# Sheet1.net
KiCad netlist of a schematic drawn in Altium Designer
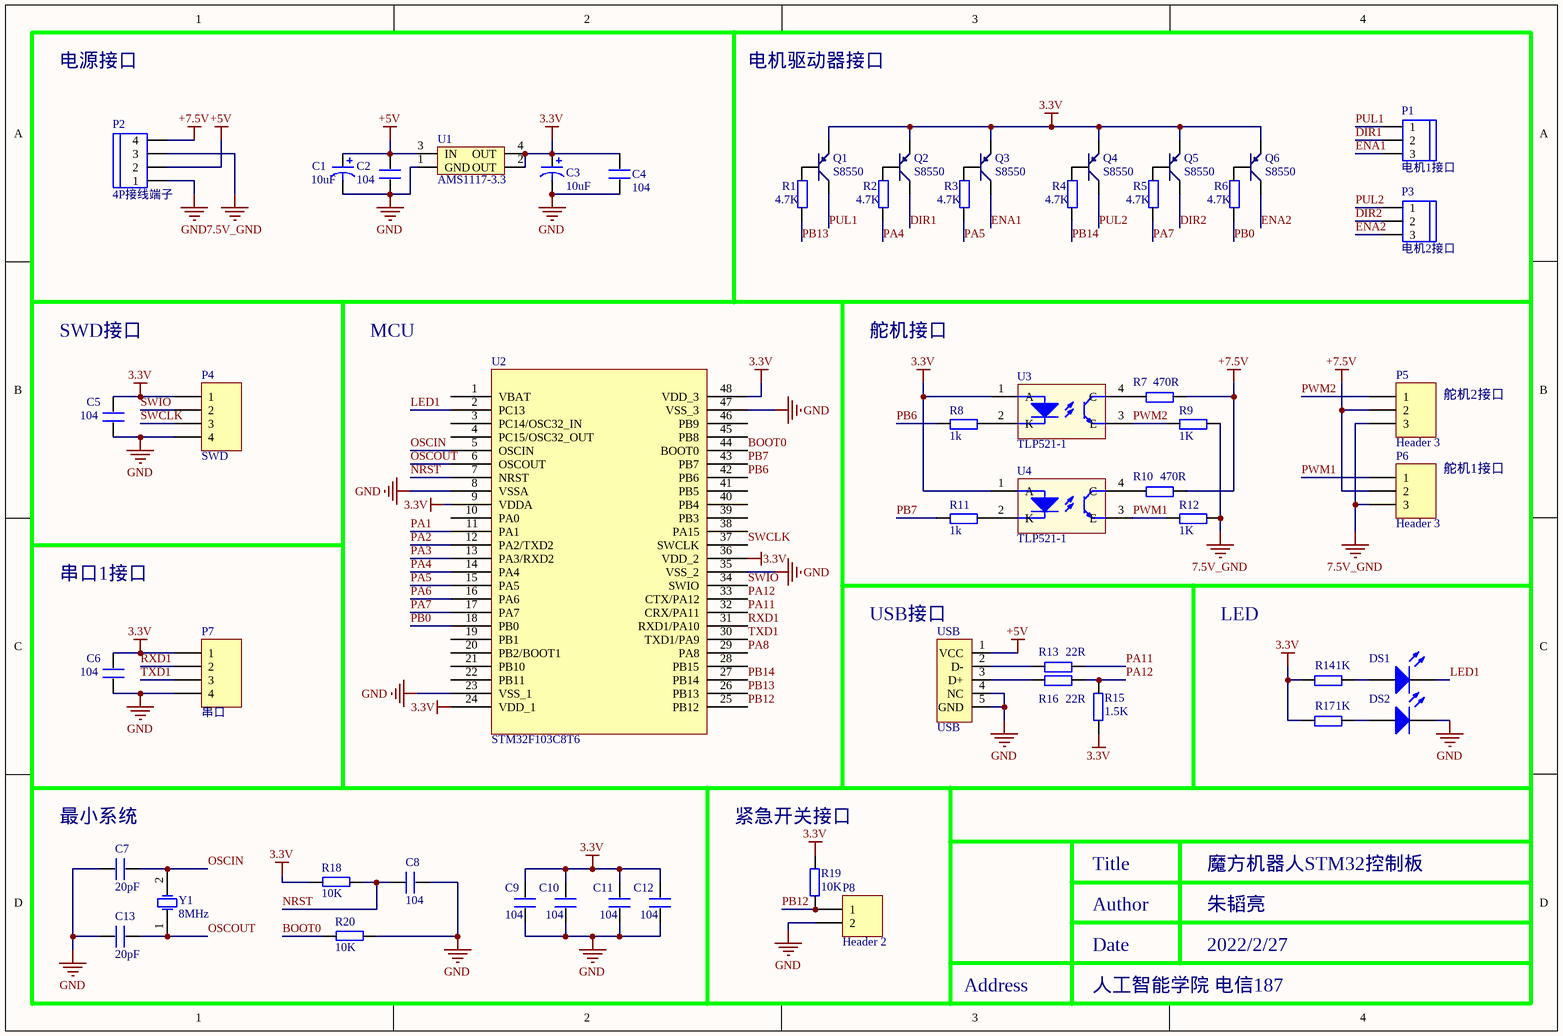
[diagram p0: Sheet1.SchDoc]

(export (version "E")
  (design (tool "Eeschema 10.0.6"))
  (components
    (comp (ref "C1")
      (value "10uF")
      (footprint "钽电容")
      (fields (field (name "Comment") "Cap Pol"))
      (libsource (lib "mylib") (part "Cap Pol"))
    )
    (comp (ref "C2") (value "104") (footprint "0805C") (libsource (lib "Explorer STM32F407封装库") (part "C")))
    (comp (ref "C3")
      (value "10uF")
      (footprint "钽电容")
      (fields (field (name "Comment") "Cap Pol"))
      (libsource (lib "mylib") (part "Cap Pol"))
    )
    (comp (ref "C4") (value "104") (footprint "0805C") (libsource (lib "Explorer STM32F407封装库") (part "C")))
    (comp (ref "C5") (value "104") (footprint "0805C") (libsource (lib "Explorer STM32F407封装库") (part "C")))
    (comp (ref "C6") (value "104") (footprint "0805C") (libsource (lib "Explorer STM32F407封装库") (part "C")))
    (comp (ref "C7") (value "20pF") (footprint "0805C") (libsource (lib "Explorer STM32F407封装库") (part "C")))
    (comp (ref "C8") (value "104") (footprint "0805C") (libsource (lib "Explorer STM32F407封装库") (part "C")))
    (comp (ref "C9") (value "104") (footprint "0805C") (libsource (lib "Explorer STM32F407封装库") (part "C")))
    (comp (ref "C10") (value "104") (footprint "0805C") (libsource (lib "Explorer STM32F407封装库") (part "C")))
    (comp (ref "C11") (value "104") (footprint "0805C") (libsource (lib "Explorer STM32F407封装库") (part "C")))
    (comp (ref "C12") (value "104") (footprint "0805C") (libsource (lib "Explorer STM32F407封装库") (part "C")))
    (comp (ref "C13") (value "20pF") (footprint "0805C") (libsource (lib "Explorer STM32F407封装库") (part "C")))
    (comp (ref "DS1")
      (value "LED1")
      (footprint "SMDLED")
      (description "Typical RED, GREEN, YELLOW, AMBER GaAs LED")
      (fields (field (name "PUBLISHER") "Altium Limited"))
      (libsource (lib "EliteSTM32封装库") (part "LED2"))
    )
    (comp (ref "DS2")
      (value "LED1")
      (footprint "SMDLED")
      (description "Typical RED, GREEN, YELLOW, AMBER GaAs LED")
      (fields (field (name "PUBLISHER") "Altium Limited"))
      (libsource (lib "EliteSTM32封装库") (part "LED2"))
    )
    (comp (ref "P1") (value "电机1接口") (footprint "KF301-3P") (libsource (lib "mylib") (part "3P接线端子")))
    (comp (ref "P2") (value "4P接线端子") (footprint "KF301-4P") (libsource (lib "mylib") (part "4P接线端子")))
    (comp (ref "P3") (value "电机2接口") (footprint "KF301-3P") (libsource (lib "mylib") (part "3P接线端子")))
    (comp (ref "P4")
      (value "SWD")
      (footprint "HDR1X4")
      (description "Header, 4-Pin")
      (fields (field (name "PUBLISHER") "Altium Limited"))
      (libsource (lib "Miscellaneous Connectors") (part "Header 4"))
    )
    (comp (ref "P5")
      (value "Header 3")
      (footprint "HDR1X3")
      (description "Header, 3-Pin")
      (fields (field (name "PUBLISHER") "Altium Limited"))
      (libsource (lib "Miscellaneous Connectors") (part "Header 3"))
    )
    (comp (ref "P6")
      (value "Header 3")
      (footprint "HDR1X3")
      (description "Header, 3-Pin")
      (fields (field (name "PUBLISHER") "Altium Limited"))
      (libsource (lib "Miscellaneous Connectors") (part "Header 3"))
    )
    (comp (ref "P7")
      (value "串口")
      (footprint "HDR1X4")
      (description "Header, 4-Pin")
      (fields (field (name "PUBLISHER") "Altium Limited"))
      (libsource (lib "Miscellaneous Connectors") (part "Header 4"))
    )
    (comp (ref "P8")
      (value "Header 2")
      (footprint "HDR1X2")
      (description "Header, 2-Pin")
      (fields (field (name "PUBLISHER") "Altium Limited"))
      (libsource (lib "Miscellaneous Connectors") (part "Header 2"))
    )
    (comp (ref "Q1")
      (value "S8550")
      (footprint "SOT-23R")
      (description "8550/BCW68")
      (libsource (lib "EliteSTM32封装库") (part "PNP"))
    )
    (comp (ref "Q2")
      (value "S8550")
      (footprint "SOT-23R")
      (description "8550/BCW68")
      (libsource (lib "EliteSTM32封装库") (part "PNP"))
    )
    (comp (ref "Q3")
      (value "S8550")
      (footprint "SOT-23R")
      (description "8550/BCW68")
      (libsource (lib "EliteSTM32封装库") (part "PNP"))
    )
    (comp (ref "Q4")
      (value "S8550")
      (footprint "SOT-23R")
      (description "8550/BCW68")
      (libsource (lib "EliteSTM32封装库") (part "PNP"))
    )
    (comp (ref "Q5")
      (value "S8550")
      (footprint "SOT-23R")
      (description "8550/BCW68")
      (libsource (lib "EliteSTM32封装库") (part "PNP"))
    )
    (comp (ref "Q6")
      (value "S8550")
      (footprint "SOT-23R")
      (description "8550/BCW68")
      (libsource (lib "EliteSTM32封装库") (part "PNP"))
    )
    (comp (ref "R1") (value "4.7K") (footprint "0805") (libsource (lib "EliteSTM32封装库") (part "R_1")))
    (comp (ref "R2") (value "4.7K") (footprint "0805") (libsource (lib "EliteSTM32封装库") (part "R_1")))
    (comp (ref "R3") (value "4.7K") (footprint "0805") (libsource (lib "EliteSTM32封装库") (part "R_1")))
    (comp (ref "R4") (value "4.7K") (footprint "0805") (libsource (lib "EliteSTM32封装库") (part "R_1")))
    (comp (ref "R5") (value "4.7K") (footprint "0805") (libsource (lib "EliteSTM32封装库") (part "R_1")))
    (comp (ref "R6") (value "4.7K") (footprint "0805") (libsource (lib "EliteSTM32封装库") (part "R_1")))
    (comp (ref "R7") (value "470R") (footprint "0805") (libsource (lib "EliteSTM32封装库") (part "R_1")))
    (comp (ref "R8") (value "1k") (footprint "0805") (libsource (lib "EliteSTM32封装库") (part "R_1")))
    (comp (ref "R9") (value "1K") (footprint "0805") (libsource (lib "EliteSTM32封装库") (part "R_1")))
    (comp (ref "R10") (value "470R") (footprint "0805") (libsource (lib "EliteSTM32封装库") (part "R_1")))
    (comp (ref "R11") (value "1k") (footprint "0805") (libsource (lib "EliteSTM32封装库") (part "R_1")))
    (comp (ref "R12") (value "1K") (footprint "0805") (libsource (lib "EliteSTM32封装库") (part "R_1")))
    (comp (ref "R13") (value "22R") (footprint "0805") (libsource (lib "EliteSTM32封装库") (part "R_1")))
    (comp (ref "R14") (value "1K") (footprint "0805") (libsource (lib "EliteSTM32封装库") (part "R_1")))
    (comp (ref "R15") (value "1.5K") (footprint "0805") (libsource (lib "EliteSTM32封装库") (part "R_1")))
    (comp (ref "R16") (value "22R") (footprint "0805") (libsource (lib "EliteSTM32封装库") (part "R_1")))
    (comp (ref "R17") (value "1K") (footprint "0805") (libsource (lib "EliteSTM32封装库") (part "R_1")))
    (comp (ref "R18") (value "10K") (footprint "0805") (libsource (lib "EliteSTM32封装库") (part "R_1")))
    (comp (ref "R19") (value "10K") (footprint "0805") (libsource (lib "EliteSTM32封装库") (part "R_1")))
    (comp (ref "R20") (value "10K") (footprint "0805") (libsource (lib "EliteSTM32封装库") (part "R_1")))
    (comp (ref "U1")
      (value "AMS1117-3.3")
      (footprint "AMS1117")
      (libsource (lib "EliteSTM32封装库") (part "AMS1117"))
    )
    (comp (ref "U2")
      (value "STM32F103C8T6")
      (footprint "LQF48")
      (libsource (lib "mylib") (part "STM32F103C8T6"))
    )
    (comp (ref "U3")
      (value "TLP521-1")
      (footprint "SOP-4_(TLP521)")
      (libsource (lib "mylib") (part "TLP521-1"))
    )
    (comp (ref "U4")
      (value "TLP521-1")
      (footprint "SOP-4_(TLP521)")
      (libsource (lib "mylib") (part "TLP521-1"))
    )
    (comp (ref "USB")
      (value "USB")
      (footprint "USB/SM0.8-6H5")
      (libsource (lib "EliteSTM32封装库") (part "USB5"))
    )
    (comp (ref "Y1") (value "8MHz") (footprint "SMD-5032") (libsource (lib "EliteSTM32封装库") (part "XTAL")))
  )
  (nets
    (net (code "1") (name "+5V") (class "Default")
      (node (ref "C1") (pin "1") (pinfunction "1_1") (pintype "passive"))
      (node (ref "C2") (pin "2") (pintype "passive"))
      (node (ref "P2") (pin "2") (pinfunction "2_2") (pintype "passive"))
      (node (ref "U1") (pin "3") (pinfunction "IN_3") (pintype "passive"))
      (node (ref "USB") (pin "1") (pinfunction "VCC_1") (pintype "passive"))
    )
    (net (code "2") (name "+7.5V") (class "Default")
      (node (ref "P2") (pin "4") (pinfunction "4_4") (pintype "passive"))
      (node (ref "P5") (pin "2") (pinfunction "2_2") (pintype "passive"))
      (node (ref "P6") (pin "2") (pinfunction "2_2") (pintype "passive"))
      (node (ref "R10") (pin "2") (pintype "passive"))
      (node (ref "R7") (pin "2") (pintype "passive"))
    )
    (net (code "3") (name "/BOOT0") (class "Default")
      (node (ref "R20") (pin "2") (pintype "passive"))
      (node (ref "U2") (pin "44") (pinfunction "BOOT0_44") (pintype "passive"))
    )
    (net (code "4") (name "/DIR1") (class "Default")
      (node (ref "P1") (pin "2") (pinfunction "2_2") (pintype "passive"))
      (node (ref "Q2") (pin "3") (pinfunction "C_3") (pintype "passive"))
    )
    (net (code "5") (name "/DIR2") (class "Default")
      (node (ref "P3") (pin "2") (pinfunction "2_2") (pintype "passive"))
      (node (ref "Q5") (pin "3") (pinfunction "C_3") (pintype "passive"))
    )
    (net (code "6") (name "/ENA1") (class "Default")
      (node (ref "P1") (pin "3") (pinfunction "3_3") (pintype "passive"))
      (node (ref "Q3") (pin "3") (pinfunction "C_3") (pintype "passive"))
    )
    (net (code "7") (name "/ENA2") (class "Default")
      (node (ref "P3") (pin "3") (pinfunction "3_3") (pintype "passive"))
      (node (ref "Q6") (pin "3") (pinfunction "C_3") (pintype "passive"))
    )
    (net (code "8") (name "/LED1") (class "Default")
      (node (ref "DS1") (pin "2") (pinfunction "K_2") (pintype "passive"))
      (node (ref "U2") (pin "2") (pinfunction "PC13_2") (pintype "passive"))
    )
    (net (code "9") (name "/NRST") (class "Default")
      (node (ref "C8") (pin "1") (pintype "passive"))
      (node (ref "R18") (pin "1") (pintype "passive"))
      (node (ref "U2") (pin "7") (pinfunction "NRST_7") (pintype "passive"))
    )
    (net (code "10") (name "/OSCIN") (class "Default")
      (node (ref "C7") (pin "2") (pintype "passive"))
      (node (ref "U2") (pin "5") (pinfunction "OSCIN_5") (pintype "passive"))
      (node (ref "Y1") (pin "2") (pinfunction "2_2") (pintype "passive"))
    )
    (net (code "11") (name "/OSCOUT") (class "Default")
      (node (ref "C13") (pin "2") (pintype "passive"))
      (node (ref "U2") (pin "6") (pinfunction "OSCOUT_6") (pintype "passive"))
      (node (ref "Y1") (pin "1") (pinfunction "1_1") (pintype "passive"))
    )
    (net (code "12") (name "/PA1") (class "Default")
      (node (ref "U2") (pin "11") (pinfunction "PA1_11") (pintype "passive"))
    )
    (net (code "13") (name "/PA2") (class "Default")
      (node (ref "U2") (pin "12") (pinfunction "PA2/TXD2_12") (pintype "passive"))
    )
    (net (code "14") (name "/PA3") (class "Default")
      (node (ref "U2") (pin "13") (pinfunction "PA3/RXD2_13") (pintype "passive"))
    )
    (net (code "15") (name "/PA4") (class "Default")
      (node (ref "R2") (pin "1") (pintype "passive"))
      (node (ref "U2") (pin "14") (pinfunction "PA4_14") (pintype "passive"))
    )
    (net (code "16") (name "/PA5") (class "Default")
      (node (ref "R3") (pin "1") (pintype "passive"))
      (node (ref "U2") (pin "15") (pinfunction "PA5_15") (pintype "passive"))
    )
    (net (code "17") (name "/PA6") (class "Default")
      (node (ref "U2") (pin "16") (pinfunction "PA6_16") (pintype "passive"))
    )
    (net (code "18") (name "/PA7") (class "Default")
      (node (ref "R5") (pin "1") (pintype "passive"))
      (node (ref "U2") (pin "17") (pinfunction "PA7_17") (pintype "passive"))
    )
    (net (code "19") (name "/PA8") (class "Default")
      (node (ref "U2") (pin "29") (pinfunction "PA8_29") (pintype "passive"))
    )
    (net (code "20") (name "/PA11") (class "Default")
      (node (ref "R13") (pin "2") (pintype "passive"))
      (node (ref "U2") (pin "32") (pinfunction "CRX/PA11_32") (pintype "passive"))
    )
    (net (code "21") (name "/PA12") (class "Default")
      (node (ref "R15") (pin "1") (pintype "passive"))
      (node (ref "R16") (pin "2") (pintype "passive"))
      (node (ref "U2") (pin "33") (pinfunction "CTX/PA12_33") (pintype "passive"))
    )
    (net (code "22") (name "/PB0") (class "Default")
      (node (ref "R6") (pin "1") (pintype "passive"))
      (node (ref "U2") (pin "18") (pinfunction "PB0_18") (pintype "passive"))
    )
    (net (code "23") (name "/PB6") (class "Default")
      (node (ref "R8") (pin "1") (pintype "passive"))
      (node (ref "U2") (pin "42") (pinfunction "PB6_42") (pintype "passive"))
    )
    (net (code "24") (name "/PB7") (class "Default")
      (node (ref "R11") (pin "1") (pintype "passive"))
      (node (ref "U2") (pin "43") (pinfunction "PB7_43") (pintype "passive"))
    )
    (net (code "25") (name "/PB12") (class "Default")
      (node (ref "P8") (pin "1") (pinfunction "1_1") (pintype "passive"))
      (node (ref "R19") (pin "2") (pintype "passive"))
      (node (ref "U2") (pin "25") (pinfunction "PB12_25") (pintype "passive"))
    )
    (net (code "26") (name "/PB13") (class "Default")
      (node (ref "R1") (pin "1") (pintype "passive"))
      (node (ref "U2") (pin "26") (pinfunction "PB13_26") (pintype "passive"))
    )
    (net (code "27") (name "/PB14") (class "Default")
      (node (ref "R4") (pin "1") (pintype "passive"))
      (node (ref "U2") (pin "27") (pinfunction "PB14_27") (pintype "passive"))
    )
    (net (code "28") (name "/PUL1") (class "Default")
      (node (ref "P1") (pin "1") (pinfunction "1_1") (pintype "passive"))
      (node (ref "Q1") (pin "3") (pinfunction "C_3") (pintype "passive"))
    )
    (net (code "29") (name "/PUL2") (class "Default")
      (node (ref "P3") (pin "1") (pinfunction "1_1") (pintype "passive"))
      (node (ref "Q4") (pin "3") (pinfunction "C_3") (pintype "passive"))
    )
    (net (code "30") (name "/PWM1") (class "Default")
      (node (ref "P6") (pin "1") (pinfunction "1_1") (pintype "passive"))
      (node (ref "R12") (pin "1") (pintype "passive"))
      (node (ref "U4") (pin "3") (pinfunction "E_3") (pintype "passive"))
    )
    (net (code "31") (name "/PWM2") (class "Default")
      (node (ref "P5") (pin "1") (pinfunction "1_1") (pintype "passive"))
      (node (ref "R9") (pin "1") (pintype "passive"))
      (node (ref "U3") (pin "3") (pinfunction "E_3") (pintype "passive"))
    )
    (net (code "32") (name "/RXD1") (class "Default")
      (node (ref "P7") (pin "2") (pinfunction "2_2") (pintype "passive"))
      (node (ref "U2") (pin "31") (pinfunction "RXD1/PA10_31") (pintype "passive"))
    )
    (net (code "33") (name "/SWCLK") (class "Default")
      (node (ref "P4") (pin "3") (pinfunction "3_3") (pintype "passive"))
      (node (ref "U2") (pin "37") (pinfunction "SWCLK_37") (pintype "passive"))
    )
    (net (code "34") (name "/SWIO") (class "Default")
      (node (ref "P4") (pin "2") (pinfunction "2_2") (pintype "passive"))
      (node (ref "U2") (pin "34") (pinfunction "SWIO_34") (pintype "passive"))
    )
    (net (code "35") (name "/TXD1") (class "Default")
      (node (ref "P7") (pin "3") (pinfunction "3_3") (pintype "passive"))
      (node (ref "U2") (pin "30") (pinfunction "TXD1/PA9_30") (pintype "passive"))
    )
    (net (code "36") (name "3.3V") (class "Default")
      (node (ref "C10") (pin "1") (pintype "passive"))
      (node (ref "C11") (pin "1") (pintype "passive"))
      (node (ref "C12") (pin "1") (pintype "passive"))
      (node (ref "C3") (pin "1") (pinfunction "1_1") (pintype "passive"))
      (node (ref "C4") (pin "2") (pintype "passive"))
      (node (ref "C5") (pin "1") (pintype "passive"))
      (node (ref "C6") (pin "1") (pintype "passive"))
      (node (ref "C9") (pin "1") (pintype "passive"))
      (node (ref "P4") (pin "1") (pinfunction "1_1") (pintype "passive"))
      (node (ref "P7") (pin "1") (pinfunction "1_1") (pintype "passive"))
      (node (ref "Q1") (pin "1") (pinfunction "E_1") (pintype "passive"))
      (node (ref "Q2") (pin "1") (pinfunction "E_1") (pintype "passive"))
      (node (ref "Q3") (pin "1") (pinfunction "E_1") (pintype "passive"))
      (node (ref "Q4") (pin "1") (pinfunction "E_1") (pintype "passive"))
      (node (ref "Q5") (pin "1") (pinfunction "E_1") (pintype "passive"))
      (node (ref "Q6") (pin "1") (pinfunction "E_1") (pintype "passive"))
      (node (ref "R14") (pin "1") (pintype "passive"))
      (node (ref "R15") (pin "2") (pintype "passive"))
      (node (ref "R17") (pin "1") (pintype "passive"))
      (node (ref "R18") (pin "2") (pintype "passive"))
      (node (ref "R19") (pin "1") (pintype "passive"))
      (node (ref "U1") (pin "2") (pinfunction "OUT_2") (pintype "passive"))
      (node (ref "U1") (pin "4") (pinfunction "OUT_4") (pintype "passive"))
      (node (ref "U2") (pin "24") (pinfunction "VDD_1_24") (pintype "passive"))
      (node (ref "U2") (pin "36") (pinfunction "VDD_2_36") (pintype "passive"))
      (node (ref "U2") (pin "48") (pinfunction "VDD_3_48") (pintype "passive"))
      (node (ref "U2") (pin "9") (pinfunction "VDDA_9") (pintype "passive"))
      (node (ref "U3") (pin "1") (pinfunction "A_1") (pintype "passive"))
      (node (ref "U4") (pin "1") (pinfunction "A_1") (pintype "passive"))
    )
    (net (code "37") (name "7.5V_GND") (class "Default")
      (node (ref "P2") (pin "3") (pinfunction "3_3") (pintype "passive"))
      (node (ref "P5") (pin "3") (pinfunction "3_3") (pintype "passive"))
      (node (ref "P6") (pin "3") (pinfunction "3_3") (pintype "passive"))
      (node (ref "R12") (pin "2") (pintype "passive"))
      (node (ref "R9") (pin "2") (pintype "passive"))
    )
    (net (code "38") (name "GND") (class "Default")
      (node (ref "C1") (pin "2") (pinfunction "2_2") (pintype "passive"))
      (node (ref "C10") (pin "2") (pintype "passive"))
      (node (ref "C11") (pin "2") (pintype "passive"))
      (node (ref "C12") (pin "2") (pintype "passive"))
      (node (ref "C13") (pin "1") (pintype "passive"))
      (node (ref "C2") (pin "1") (pintype "passive"))
      (node (ref "C3") (pin "2") (pinfunction "2_2") (pintype "passive"))
      (node (ref "C4") (pin "1") (pintype "passive"))
      (node (ref "C5") (pin "2") (pintype "passive"))
      (node (ref "C6") (pin "2") (pintype "passive"))
      (node (ref "C7") (pin "1") (pintype "passive"))
      (node (ref "C8") (pin "2") (pintype "passive"))
      (node (ref "C9") (pin "2") (pintype "passive"))
      (node (ref "DS2") (pin "2") (pinfunction "K_2") (pintype "passive"))
      (node (ref "P2") (pin "1") (pinfunction "1_1") (pintype "passive"))
      (node (ref "P4") (pin "4") (pinfunction "4_4") (pintype "passive"))
      (node (ref "P7") (pin "4") (pinfunction "4_4") (pintype "passive"))
      (node (ref "P8") (pin "2") (pinfunction "2_2") (pintype "passive"))
      (node (ref "R20") (pin "1") (pintype "passive"))
      (node (ref "U1") (pin "1") (pinfunction "GND_1") (pintype "passive"))
      (node (ref "U2") (pin "23") (pinfunction "VSS_1_23") (pintype "passive"))
      (node (ref "U2") (pin "35") (pinfunction "VSS_2_35") (pintype "passive"))
      (node (ref "U2") (pin "47") (pinfunction "VSS_3_47") (pintype "passive"))
      (node (ref "U2") (pin "8") (pinfunction "VSSA_8") (pintype "passive"))
      (node (ref "USB") (pin "4") (pinfunction "NC_4") (pintype "passive"))
      (node (ref "USB") (pin "5") (pinfunction "GND_5") (pintype "passive"))
    )
    (net (code "39") (name "Net-(DS1-A)") (class "Default")
      (node (ref "DS1") (pin "1") (pinfunction "A_1") (pintype "passive"))
      (node (ref "R14") (pin "2") (pintype "passive"))
    )
    (net (code "40") (name "Net-(DS2-A)") (class "Default")
      (node (ref "DS2") (pin "1") (pinfunction "A_1") (pintype "passive"))
      (node (ref "R17") (pin "2") (pintype "passive"))
    )
    (net (code "41") (name "Net-(Q1-B)") (class "Default")
      (node (ref "Q1") (pin "2") (pinfunction "B_2") (pintype "passive"))
      (node (ref "R1") (pin "2") (pintype "passive"))
    )
    (net (code "42") (name "Net-(Q2-B)") (class "Default")
      (node (ref "Q2") (pin "2") (pinfunction "B_2") (pintype "passive"))
      (node (ref "R2") (pin "2") (pintype "passive"))
    )
    (net (code "43") (name "Net-(Q3-B)") (class "Default")
      (node (ref "Q3") (pin "2") (pinfunction "B_2") (pintype "passive"))
      (node (ref "R3") (pin "2") (pintype "passive"))
    )
    (net (code "44") (name "Net-(Q4-B)") (class "Default")
      (node (ref "Q4") (pin "2") (pinfunction "B_2") (pintype "passive"))
      (node (ref "R4") (pin "2") (pintype "passive"))
    )
    (net (code "45") (name "Net-(Q5-B)") (class "Default")
      (node (ref "Q5") (pin "2") (pinfunction "B_2") (pintype "passive"))
      (node (ref "R5") (pin "2") (pintype "passive"))
    )
    (net (code "46") (name "Net-(Q6-B)") (class "Default")
      (node (ref "Q6") (pin "2") (pinfunction "B_2") (pintype "passive"))
      (node (ref "R6") (pin "2") (pintype "passive"))
    )
    (net (code "47") (name "Net-(U3-C)") (class "Default")
      (node (ref "R7") (pin "1") (pintype "passive"))
      (node (ref "U3") (pin "4") (pinfunction "C_4") (pintype "passive"))
    )
    (net (code "48") (name "Net-(U3-K)") (class "Default")
      (node (ref "R8") (pin "2") (pintype "passive"))
      (node (ref "U3") (pin "2") (pinfunction "K_2") (pintype "passive"))
    )
    (net (code "49") (name "Net-(U4-C)") (class "Default")
      (node (ref "R10") (pin "1") (pintype "passive"))
      (node (ref "U4") (pin "4") (pinfunction "C_4") (pintype "passive"))
    )
    (net (code "50") (name "Net-(U4-K)") (class "Default")
      (node (ref "R11") (pin "2") (pintype "passive"))
      (node (ref "U4") (pin "2") (pinfunction "K_2") (pintype "passive"))
    )
    (net (code "51") (name "Net-(USB-D+)") (class "Default")
      (node (ref "R16") (pin "1") (pintype "passive"))
      (node (ref "USB") (pin "3") (pinfunction "D+_3") (pintype "passive"))
    )
    (net (code "52") (name "Net-(USB-D-)") (class "Default")
      (node (ref "R13") (pin "1") (pintype "passive"))
      (node (ref "USB") (pin "2") (pinfunction "D-_2") (pintype "passive"))
    )
    (net (code "53") (name "unconnected-(U2-PA0-Pad10)") (class "Default")
      (node (ref "U2") (pin "10") (pinfunction "PA0_10") (pintype "passive"))
    )
    (net (code "54") (name "unconnected-(U2-PA15-Pad38)") (class "Default")
      (node (ref "U2") (pin "38") (pinfunction "PA15_38") (pintype "passive"))
    )
    (net (code "55") (name "unconnected-(U2-PB1-Pad19)") (class "Default")
      (node (ref "U2") (pin "19") (pinfunction "PB1_19") (pintype "passive"))
    )
    (net (code "56") (name "unconnected-(U2-PB2{slash}BOOT1-Pad20)") (class "Default")
      (node (ref "U2") (pin "20") (pinfunction "PB2/BOOT1_20") (pintype "passive"))
    )
    (net (code "57") (name "unconnected-(U2-PB3-Pad39)") (class "Default")
      (node (ref "U2") (pin "39") (pinfunction "PB3_39") (pintype "passive"))
    )
    (net (code "58") (name "unconnected-(U2-PB4-Pad40)") (class "Default")
      (node (ref "U2") (pin "40") (pinfunction "PB4_40") (pintype "passive"))
    )
    (net (code "59") (name "unconnected-(U2-PB5-Pad41)") (class "Default")
      (node (ref "U2") (pin "41") (pinfunction "PB5_41") (pintype "passive"))
    )
    (net (code "60") (name "unconnected-(U2-PB8-Pad45)") (class "Default")
      (node (ref "U2") (pin "45") (pinfunction "PB8_45") (pintype "passive"))
    )
    (net (code "61") (name "unconnected-(U2-PB9-Pad46)") (class "Default")
      (node (ref "U2") (pin "46") (pinfunction "PB9_46") (pintype "passive"))
    )
    (net (code "62") (name "unconnected-(U2-PB10-Pad21)") (class "Default")
      (node (ref "U2") (pin "21") (pinfunction "PB10_21") (pintype "passive"))
    )
    (net (code "63") (name "unconnected-(U2-PB11-Pad22)") (class "Default")
      (node (ref "U2") (pin "22") (pinfunction "PB11_22") (pintype "passive"))
    )
    (net (code "64") (name "unconnected-(U2-PB15-Pad28)") (class "Default")
      (node (ref "U2") (pin "28") (pinfunction "PB15_28") (pintype "passive"))
    )
    (net (code "65") (name "unconnected-(U2-PC14{slash}OSC32_IN-Pad3)") (class "Default")
      (node (ref "U2") (pin "3") (pinfunction "PC14/OSC32_IN_3") (pintype "passive"))
    )
    (net (code "66") (name "unconnected-(U2-PC15{slash}OSC32_OUT-Pad4)") (class "Default")
      (node (ref "U2") (pin "4") (pinfunction "PC15/OSC32_OUT_4") (pintype "passive"))
    )
    (net (code "67") (name "unconnected-(U2-VBAT-Pad1)") (class "Default")
      (node (ref "U2") (pin "1") (pinfunction "VBAT_1") (pintype "power_in"))
    )
  )
)
